# RX.net
KiCad netlist of a schematic drawn in Altium Designer
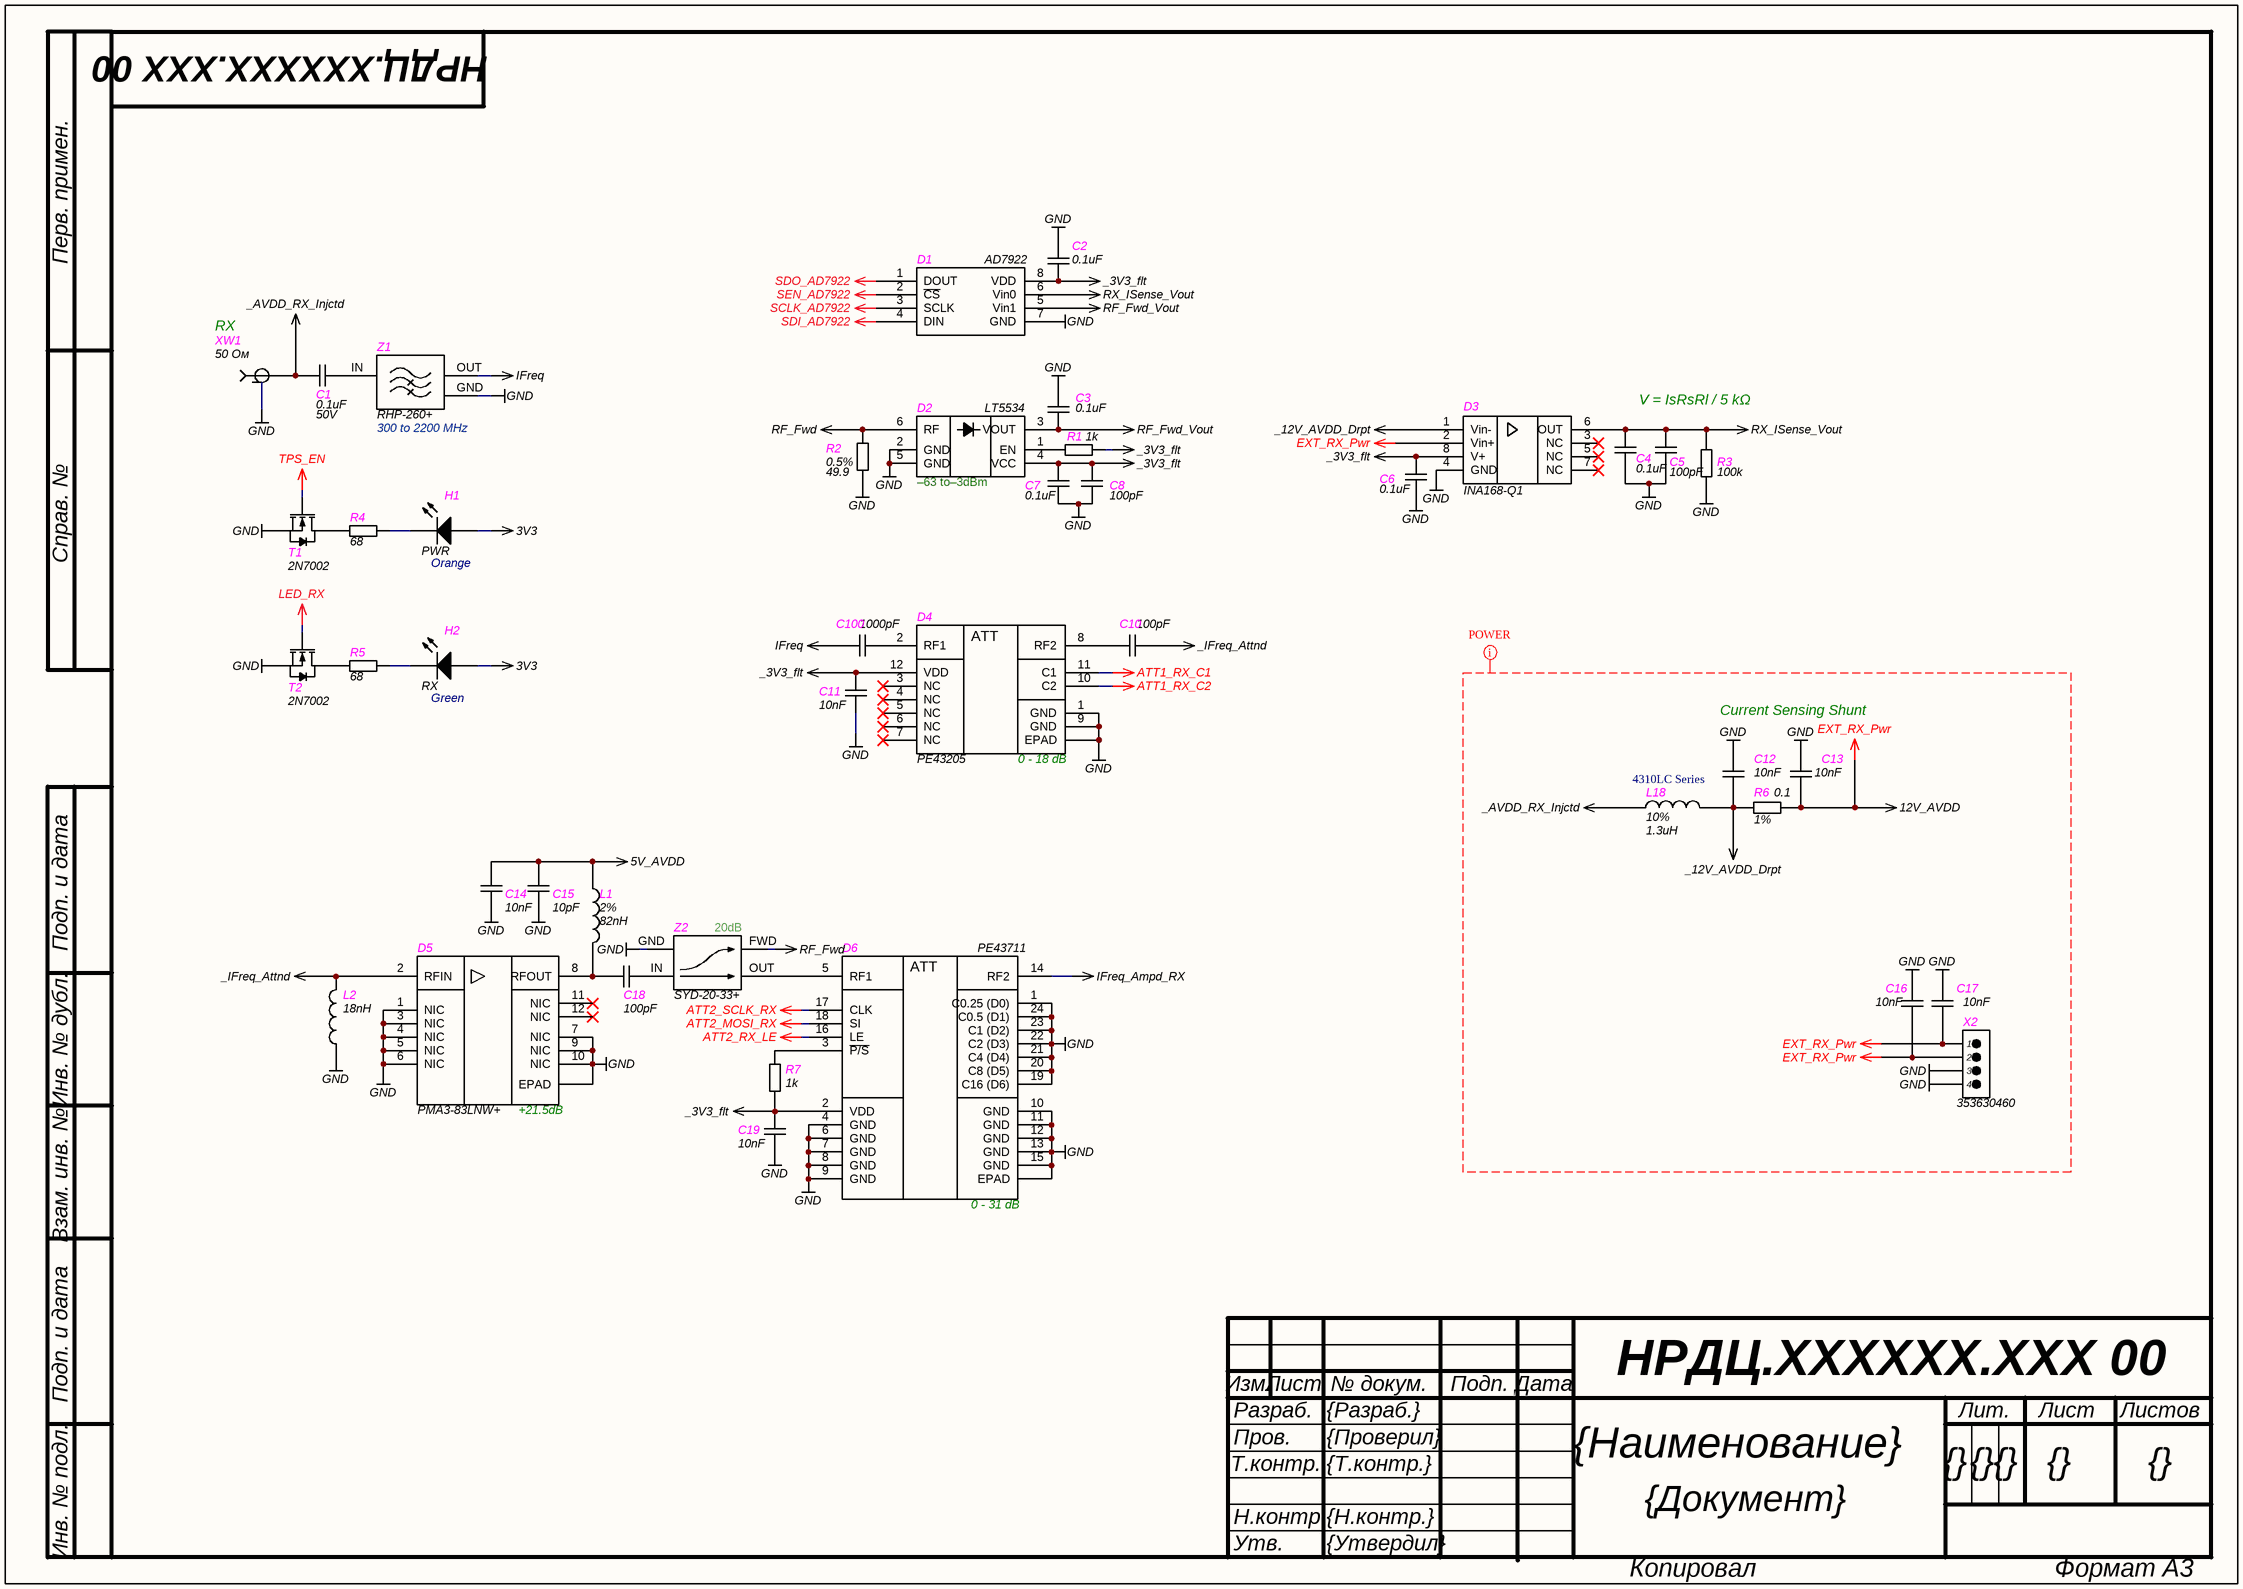
[diagram p0: RX.SchDoc]

(export (version "E")
  (design (tool "Eeschema 10.0.6"))
  (components
    (comp (ref "C1")
      (value "0.1uF")
      (footprint "C1206")
      (description "SMD Capacitor")
      (fields
        (field (name "MANUFACTURER") "Murata")
        (field (name "TOLERANCE") "5%")
        (field (name "VOLTAGE") "50V")
      )
      (libsource (lib "Kintex_SDR") (part "CAP"))
    )
    (comp (ref "C2")
      (value "0.1uF")
      (footprint "C0402")
      (description "SMD Capacitor")
      (fields (field (name "MANUFACTURER") "Murata") (field (name "TOLERANCE") "10%"))
      (libsource (lib "Kintex_SDR") (part "CAP"))
    )
    (comp (ref "C3")
      (value "0.1uF")
      (footprint "C0402")
      (description "SMD Capacitor")
      (fields (field (name "MANUFACTURER") "Murata") (field (name "TOLERANCE") "10%"))
      (libsource (lib "Kintex_SDR") (part "CAP"))
    )
    (comp (ref "C4")
      (value "0.1uF")
      (footprint "C0402")
      (description "SMD Capacitor")
      (fields (field (name "MANUFACTURER") "Murata") (field (name "TOLERANCE") "10%"))
      (libsource (lib "Kintex_SDR") (part "CAP"))
    )
    (comp (ref "C5")
      (value "100pF")
      (footprint "C0402")
      (description "SMD Capacitor")
      (fields (field (name "MANUFACTURER") "Murata") (field (name "TOLERANCE") "1%"))
      (libsource (lib "Kintex_SDR") (part "CAP"))
    )
    (comp (ref "C6")
      (value "0.1uF")
      (footprint "C0402")
      (description "SMD Capacitor")
      (fields (field (name "MANUFACTURER") "Murata") (field (name "TOLERANCE") "10%"))
      (libsource (lib "Kintex_SDR") (part "CAP"))
    )
    (comp (ref "C7")
      (value "0.1uF")
      (footprint "C0402")
      (description "SMD Capacitor")
      (fields (field (name "MANUFACTURER") "Murata") (field (name "TOLERANCE") "10%"))
      (libsource (lib "Kintex_SDR") (part "CAP"))
    )
    (comp (ref "C8")
      (value "100pF")
      (footprint "C0402")
      (description "SMD Capacitor")
      (fields (field (name "MANUFACTURER") "Murata") (field (name "TOLERANCE") "1%"))
      (libsource (lib "Kintex_SDR") (part "CAP"))
    )
    (comp (ref "C10")
      (value "100pF")
      (footprint "C0402")
      (description "SMD Capacitor")
      (fields (field (name "MANUFACTURER") "Murata") (field (name "TOLERANCE") "1%"))
      (libsource (lib "Kintex_SDR") (part "CAP"))
    )
    (comp (ref "C11")
      (value "10nF")
      (footprint "C0402")
      (description "SMD Capacitor")
      (fields (field (name "MANUFACTURER") "Murata") (field (name "TOLERANCE") "10%"))
      (libsource (lib "Kintex_SDR") (part "CAP"))
    )
    (comp (ref "C12")
      (value "10nF")
      (footprint "C0402")
      (description "SMD Capacitor")
      (fields (field (name "MANUFACTURER") "Murata") (field (name "TOLERANCE") "10%"))
      (libsource (lib "Kintex_SDR") (part "CAP"))
    )
    (comp (ref "C13")
      (value "10nF")
      (footprint "C0402")
      (description "SMD Capacitor")
      (fields (field (name "MANUFACTURER") "Murata") (field (name "TOLERANCE") "10%"))
      (libsource (lib "Kintex_SDR") (part "CAP"))
    )
    (comp (ref "C14")
      (value "10nF")
      (footprint "C0402")
      (description "SMD Capacitor")
      (fields (field (name "MANUFACTURER") "Murata") (field (name "TOLERANCE") "10%"))
      (libsource (lib "Kintex_SDR") (part "CAP"))
    )
    (comp (ref "C15")
      (value "10pF")
      (footprint "C0402")
      (description "SMD Capacitor")
      (fields (field (name "MANUFACTURER") "Murata") (field (name "TOLERANCE") "1%"))
      (libsource (lib "Kintex_SDR") (part "CAP"))
    )
    (comp (ref "C16")
      (value "10nF")
      (footprint "C0402")
      (description "SMD Capacitor")
      (fields (field (name "MANUFACTURER") "Murata") (field (name "TOLERANCE") "10%"))
      (libsource (lib "Kintex_SDR") (part "CAP"))
    )
    (comp (ref "C17")
      (value "10nF")
      (footprint "C0402")
      (description "SMD Capacitor")
      (fields (field (name "MANUFACTURER") "Murata") (field (name "TOLERANCE") "10%"))
      (libsource (lib "Kintex_SDR") (part "CAP"))
    )
    (comp (ref "C18")
      (value "100pF")
      (footprint "C0402")
      (description "SMD Capacitor")
      (fields (field (name "MANUFACTURER") "Murata") (field (name "TOLERANCE") "1%"))
      (libsource (lib "Kintex_SDR") (part "CAP"))
    )
    (comp (ref "C19")
      (value "10nF")
      (footprint "C0402")
      (description "SMD Capacitor")
      (fields (field (name "MANUFACTURER") "Murata") (field (name "TOLERANCE") "10%"))
      (libsource (lib "Kintex_SDR") (part "CAP"))
    )
    (comp (ref "C100")
      (value "1000pF")
      (footprint "C0402")
      (description "SMD Capacitor")
      (fields (field (name "MANUFACTURER") "Murata") (field (name "TOLERANCE") "5%"))
      (libsource (lib "Kintex_SDR") (part "CAP"))
    )
    (comp (ref "D1")
      (value "AD7922")
      (footprint "MSOP-8")
      (description "1 MSPS, 10-/12-Bit ADC")
      (fields (field (name "MANUFACTURER") "Analog Device") (field (name "VOLTAGE") "2.35 V to 5.25 V"))
      (libsource (lib "Kintex_SDR") (part "AD79x2"))
    )
    (comp (ref "D2")
      (value "LT5534")
      (footprint "DBLib:SC70")
      (description "50MHz to 3GHz monolithic RF power\r\ndetector")
      (fields
        (field (name "MANUFACTURER") "Linear Technology")
        (field (name "VOLTAGE") "Single 2.7V to 5.25V")
        (field (name "RF INPUT POWER RANGE") "–63 to–3dBm")
      )
      (libsource (lib "DBLib") (part "LT5534"))
    )
    (comp (ref "D3")
      (value "INA168-Q1")
      (footprint "DBLib:TSSOP (8)")
      (description "Automotive-Grade, High-Side, Current-Output, Current-Shunt Monitor")
      (fields (field (name "MANUFACTURER") "Texas Instruments") (field (name "VOLTAGE") "2.7 V to 60 V"))
      (libsource (lib "DBLib") (part "INA168-Q1"))
    )
    (comp (ref "D4")
      (value "PE43205")
      (footprint "DBLib:QFN-12")
      (description "50Ω, HaRP™ technology-enhanced\r\nfast switching 2-bit RF Digital Step Attenuator")
      (fields (field (name "MANUFACTURER") "Peregrine Technical Solutions"))
      (libsource (lib "DBLib") (part "PE43205"))
    )
    (comp (ref "D5")
      (value "PMA3-83LNW+")
      (footprint "DQ1225")
      (description "PHEMT based wideband, low noise MMIC amplifier")
      (fields (field (name "MANUFACTURER") "Mini-Circuits"))
      (libsource (lib "DBLib") (part "PMA3-83LNW+"))
    )
    (comp (ref "D6")
      (value "PE43711")
      (footprint "QFN-24")
      (description "The PE43711 is a 50Ω, HaRP™ technology-enhanced, 7-bit RF digital step attenuator")
      (fields (field (name "MANUFACTURER") "Peregrine Technical Solutions"))
      (libsource (lib "DBLib") (part "PE43711"))
    )
    (comp (ref "H1")
      (value "PWR")
      (footprint "LED_0805_Green")
      (description "CHIP LED LAMP")
      (fields (field (name "MANUFACTURER") "Kingbright") (field (name "COLOR") "Orange"))
      (libsource (lib "DBLib") (part "LED"))
    )
    (comp (ref "H2")
      (value "RX")
      (footprint "LED_0805_Green")
      (description "CHIP LED LAMP")
      (fields (field (name "MANUFACTURER") "Kingbright") (field (name "COLOR") "Green"))
      (libsource (lib "DBLib") (part "LED"))
    )
    (comp (ref "L1")
      (value "82nH")
      (footprint "DBLib:L0603_HP")
      (description "Chip SMD Inductor")
      (fields
        (field (name "MANUFACTURER") "Coilcraft")
        (field (name "TOLERANCE") "2%")
        (field (name "Comment") "Inductor RF")
      )
      (libsource (lib "DBLib") (part "Inductor RF"))
    )
    (comp (ref "L2")
      (value "18nH")
      (footprint "DBLib:L0603_HP")
      (description "Chip SMD Inductor")
      (fields (field (name "MANUFACTURER") "Coilcraft") (field (name "TOLERANCE") "2%"))
      (libsource (lib "") (part "Inductor RF_1"))
    )
    (comp (ref "L18")
      (value "1.3uH")
      (footprint "DBLib:4310LC")
      (description "Chip SMD Inductor")
      (fields
        (field (name "MANUFACTURER") "Coilcraft")
        (field (name "TOLERANCE") "10%")
        (field (name "Comment") "Inductor RF")
      )
      (libsource (lib "DBLib") (part "Inductor RF"))
    )
    (comp (ref "R1")
      (value "1k")
      (footprint "R0402")
      (description "SMD Resistor")
      (fields (field (name "POWER") "0.062 Wt") (field (name "TOLERANCE") "5%"))
      (libsource (lib "") (part "RES_1"))
    )
    (comp (ref "R2")
      (value "49.9")
      (footprint "R0402")
      (description "SMD Resistor")
      (fields
        (field (name "POWER") "0.063 Wt")
        (field (name "TOLERANCE") "0.5%")
        (field (name "MANUFACTURER") "Panasonic Electronic Components")
      )
      (libsource (lib "") (part "RES_3"))
    )
    (comp (ref "R3")
      (value "100k")
      (footprint "R0402")
      (description "SMD Resistor")
      (fields (field (name "POWER") "1/5 Wt") (field (name "TOLERANCE") "1%"))
      (libsource (lib "") (part "RES_2"))
    )
    (comp (ref "R4")
      (value "68")
      (footprint "R0402")
      (description "SMD Resistor")
      (fields (field (name "POWER") "0.062 Wt") (field (name "TOLERANCE") "5%"))
      (libsource (lib "Kintex_SDR") (part "RES"))
    )
    (comp (ref "R5")
      (value "68")
      (footprint "R0402")
      (description "SMD Resistor")
      (fields (field (name "POWER") "0.062 Wt") (field (name "TOLERANCE") "5%"))
      (libsource (lib "") (part "RES_1"))
    )
    (comp (ref "R6")
      (value "0.1")
      (footprint "R0805")
      (description "SMD Resistor")
      (fields
        (field (name "POWER") "1/2 Wt")
        (field (name "TOLERANCE") "1%")
        (field (name "MANUFACTURER") "Panasonic Electronic Components")
      )
      (libsource (lib "") (part "RES_1"))
    )
    (comp (ref "R7")
      (value "1k")
      (footprint "R0402")
      (description "SMD Resistor")
      (fields (field (name "POWER") "0.062 Wt") (field (name "TOLERANCE") "5%"))
      (libsource (lib "") (part "RES_2"))
    )
    (comp (ref "T1")
      (value "2N7002")
      (footprint "SOT-23")
      (description "N-Channel MOSFET 2N7002")
      (fields (field (name "VOLTAGE") "60V"))
      (libsource (lib "Kintex_SDR") (part "2N7002"))
    )
    (comp (ref "T2")
      (value "2N7002")
      (footprint "SOT-23")
      (description "N-Channel MOSFET 2N7002")
      (fields (field (name "VOLTAGE") "60V"))
      (libsource (lib "Kintex_SDR") (part "2N7002"))
    )
    (comp (ref "X2")
      (value "353630460")
      (footprint "DBLib:CON_353630460")
      (description "2.00mm Pitch Sherlock Wire-to-Board Header, Right-Angle, with Positive Lock, 4 Circuits")
      (fields (field (name "MANUFACTURER") "Molex"))
      (libsource (lib "DBLib") (part "353630460"))
    )
    (comp (ref "XW1")
      (value "50 Ом")
      (footprint "MOLEX SD-73251-135 (Gold)")
      (description "50 Ohms, SMA Jack, Vertica")
      (fields (field (name "MANUFACTURER") "Molex"))
      (libsource (lib "DBLib") (part "RF Connector"))
    )
    (comp (ref "Z1")
      (value "RHP-260+")
      (footprint "GP731")
      (description "High Pass Filter")
      (fields (field (name "MANUFACTURER") "Mini-Circuits") (field (name "FREQUENCY") "300 to 2200 MHz"))
      (libsource (lib "DBLib") (part "RHP-260+"))
    )
    (comp (ref "Z2")
      (value "SYD-20-33+")
      (footprint "DBLib:AH202")
      (description "Directional Coupler")
      (fields (field (name "MANUFACTURER") "Mini-Circuits") (field (name "COUPLING") "20dB"))
      (libsource (lib "DBLib") (part "SYD-20-33+"))
    )
  )
  (nets
    (net (code "1") (name "3V3") (class "Default")
      (node (ref "H1") (pin "2") (pinfunction "A_2") (pintype "passive"))
      (node (ref "H2") (pin "2") (pinfunction "A_2") (pintype "passive"))
    )
    (net (code "2") (name "5V_AVDD") (class "Default")
      (node (ref "C14") (pin "2") (pinfunction "2_2") (pintype "passive"))
      (node (ref "C15") (pin "2") (pinfunction "2_2") (pintype "passive"))
      (node (ref "L1") (pin "2") (pinfunction "2_2") (pintype "passive"))
    )
    (net (code "3") (name "12V_AVDD") (class "Default")
      (node (ref "C13") (pin "1") (pinfunction "1_1") (pintype "passive"))
      (node (ref "C16") (pin "2") (pinfunction "2_2") (pintype "passive"))
      (node (ref "C17") (pin "2") (pinfunction "2_2") (pintype "passive"))
      (node (ref "D3") (pin "2") (pinfunction "Vin+_2") (pintype "passive"))
      (node (ref "R6") (pin "1") (pinfunction "1_1") (pintype "passive"))
      (node (ref "X2") (pin "1") (pinfunction "1_1") (pintype "passive"))
      (node (ref "X2") (pin "2") (pinfunction "2_2") (pintype "passive"))
    )
    (net (code "4") (name "ATT1_RX_C1") (class "Default")
      (node (ref "D4") (pin "11") (pinfunction "C1_11") (pintype "passive"))
    )
    (net (code "5") (name "ATT1_RX_C2") (class "Default")
      (node (ref "D4") (pin "10") (pinfunction "C2_10") (pintype "passive"))
    )
    (net (code "6") (name "ATT2_MOSI_RX") (class "Default")
      (node (ref "D6") (pin "18") (pinfunction "SI_18") (pintype "passive"))
    )
    (net (code "7") (name "ATT2_RX_LE") (class "Default")
      (node (ref "D6") (pin "16") (pinfunction "LE_16") (pintype "passive"))
    )
    (net (code "8") (name "ATT2_SCLK_RX") (class "Default")
      (node (ref "D6") (pin "17") (pinfunction "CLK_17") (pintype "passive"))
    )
    (net (code "9") (name "GND") (class "Default")
      (node (ref "C11") (pin "1") (pinfunction "1_1") (pintype "passive"))
      (node (ref "C12") (pin "2") (pinfunction "2_2") (pintype "passive"))
      (node (ref "C13") (pin "2") (pinfunction "2_2") (pintype "passive"))
      (node (ref "C14") (pin "1") (pinfunction "1_1") (pintype "passive"))
      (node (ref "C15") (pin "1") (pinfunction "1_1") (pintype "passive"))
      (node (ref "C16") (pin "1") (pinfunction "1_1") (pintype "passive"))
      (node (ref "C17") (pin "1") (pinfunction "1_1") (pintype "passive"))
      (node (ref "C19") (pin "1") (pinfunction "1_1") (pintype "passive"))
      (node (ref "C2") (pin "2") (pinfunction "2_2") (pintype "passive"))
      (node (ref "C3") (pin "1") (pinfunction "1_1") (pintype "passive"))
      (node (ref "C4") (pin "1") (pinfunction "1_1") (pintype "passive"))
      (node (ref "C5") (pin "1") (pinfunction "1_1") (pintype "passive"))
      (node (ref "C6") (pin "1") (pinfunction "1_1") (pintype "passive"))
      (node (ref "C7") (pin "1") (pinfunction "1_1") (pintype "passive"))
      (node (ref "C8") (pin "1") (pinfunction "1_1") (pintype "passive"))
      (node (ref "D1") (pin "7") (pinfunction "GND_7") (pintype "passive"))
      (node (ref "D2") (pin "2") (pinfunction "GND_2") (pintype "passive"))
      (node (ref "D2") (pin "5") (pinfunction "GND_5") (pintype "passive"))
      (node (ref "D3") (pin "4") (pinfunction "GND_4") (pintype "passive"))
      (node (ref "D4") (pin "1") (pinfunction "GND_1") (pintype "passive"))
      (node (ref "D4") (pin "13") (pinfunction "EPAD_13") (pintype "passive"))
      (node (ref "D4") (pin "9") (pinfunction "GND_9") (pintype "passive"))
      (node (ref "D5") (pin "1") (pinfunction "NIC_1") (pintype "passive"))
      (node (ref "D5") (pin "10") (pinfunction "NIC_10") (pintype "passive"))
      (node (ref "D5") (pin "13") (pinfunction "EPAD_13") (pintype "passive"))
      (node (ref "D5") (pin "3") (pinfunction "NIC_3") (pintype "passive"))
      (node (ref "D5") (pin "4") (pinfunction "NIC_4") (pintype "passive"))
      (node (ref "D5") (pin "5") (pinfunction "NIC_5") (pintype "passive"))
      (node (ref "D5") (pin "6") (pinfunction "NIC_6") (pintype "passive"))
      (node (ref "D5") (pin "7") (pinfunction "NIC_7") (pintype "passive"))
      (node (ref "D5") (pin "9") (pinfunction "NIC_9") (pintype "passive"))
      (node (ref "D6") (pin "1") (pinfunction "C0.25_(D0)_1") (pintype "passive"))
      (node (ref "D6") (pin "10") (pinfunction "GND_10") (pintype "passive"))
      (node (ref "D6") (pin "11") (pinfunction "GND_11") (pintype "passive"))
      (node (ref "D6") (pin "12") (pinfunction "GND_12") (pintype "passive"))
      (node (ref "D6") (pin "13") (pinfunction "GND_13") (pintype "passive"))
      (node (ref "D6") (pin "15") (pinfunction "GND_15") (pintype "passive"))
      (node (ref "D6") (pin "19") (pinfunction "C16_(D6)_19") (pintype "passive"))
      (node (ref "D6") (pin "20") (pinfunction "C8_(D5)_20") (pintype "passive"))
      (node (ref "D6") (pin "21") (pinfunction "C4_(D4)_21") (pintype "passive"))
      (node (ref "D6") (pin "22") (pinfunction "C2_(D3)_22") (pintype "passive"))
      (node (ref "D6") (pin "23") (pinfunction "C1_(D2)_23") (pintype "passive"))
      (node (ref "D6") (pin "24") (pinfunction "C0.5_(D1)_24") (pintype "passive"))
      (node (ref "D6") (pin "25") (pinfunction "EPAD_25") (pintype "passive"))
      (node (ref "D6") (pin "4") (pinfunction "GND_4") (pintype "passive"))
      (node (ref "D6") (pin "6") (pinfunction "GND_6") (pintype "passive"))
      (node (ref "D6") (pin "7") (pinfunction "GND_7") (pintype "passive"))
      (node (ref "D6") (pin "8") (pinfunction "GND_8") (pintype "passive"))
      (node (ref "D6") (pin "9") (pinfunction "GND_9") (pintype "passive"))
      (node (ref "L2") (pin "1") (pinfunction "1_1") (pintype "passive"))
      (node (ref "R2") (pin "2") (pinfunction "2_2") (pintype "passive"))
      (node (ref "R3") (pin "1") (pinfunction "1_1") (pintype "passive"))
      (node (ref "T1") (pin "2") (pinfunction "S_2") (pintype "passive"))
      (node (ref "T2") (pin "2") (pinfunction "S_2") (pintype "passive"))
      (node (ref "X2") (pin "3") (pinfunction "3_3") (pintype "passive"))
      (node (ref "X2") (pin "4") (pinfunction "4_4") (pintype "passive"))
      (node (ref "XW1") (pin "G") (pinfunction "GND_G") (pintype "passive"))
      (node (ref "Z1") (pin "GND") (pinfunction "GND_GND") (pintype "passive"))
      (node (ref "Z2") (pin "GND") (pinfunction "GND_GND") (pintype "passive"))
    )
    (net (code "10") (name "IFreq") (class "Default")
      (node (ref "C100") (pin "1") (pinfunction "1_1") (pintype "passive"))
      (node (ref "Z1") (pin "OUT") (pinfunction "OUT_OUT") (pintype "passive"))
    )
    (net (code "11") (name "IFreq_Ampd_RX") (class "Default")
      (node (ref "D6") (pin "14") (pinfunction "RF2_14") (pintype "passive"))
    )
    (net (code "12") (name "LED_RX") (class "Default")
      (node (ref "T2") (pin "1") (pinfunction "G_1") (pintype "passive"))
    )
    (net (code "13") (name "Net-(C1-Pad2)") (class "Default")
      (node (ref "C1") (pin "2") (pinfunction "2_2") (pintype "passive"))
      (node (ref "Z1") (pin "IN") (pinfunction "IN_IN") (pintype "passive"))
    )
    (net (code "14") (name "Net-(C18-Pad2)") (class "Default")
      (node (ref "C18") (pin "2") (pinfunction "2_2") (pintype "passive"))
      (node (ref "Z2") (pin "IN") (pinfunction "IN_IN") (pintype "passive"))
    )
    (net (code "15") (name "Net-(D2-EN)") (class "Default")
      (node (ref "D2") (pin "1") (pinfunction "EN_1") (pintype "passive"))
      (node (ref "R1") (pin "2") (pinfunction "2_2") (pintype "passive"))
    )
    (net (code "16") (name "Net-(D4-RF1)") (class "Default")
      (node (ref "C100") (pin "2") (pinfunction "2_2") (pintype "passive"))
      (node (ref "D4") (pin "2") (pinfunction "RF1_2") (pintype "passive"))
    )
    (net (code "17") (name "Net-(D4-RF2)") (class "Default")
      (node (ref "C10") (pin "1") (pinfunction "1_1") (pintype "passive"))
      (node (ref "D4") (pin "8") (pinfunction "RF2_8") (pintype "passive"))
    )
    (net (code "18") (name "Net-(D5-RFOUT)") (class "Default")
      (node (ref "C18") (pin "1") (pinfunction "1_1") (pintype "passive"))
      (node (ref "D5") (pin "8") (pinfunction "RFOUT_8") (pintype "passive"))
      (node (ref "L1") (pin "1") (pinfunction "1_1") (pintype "passive"))
    )
    (net (code "19") (name "Net-(D6-RF1)") (class "Default")
      (node (ref "D6") (pin "5") (pinfunction "RF1_5") (pintype "passive"))
      (node (ref "Z2") (pin "OUT") (pinfunction "OUT_OUT") (pintype "passive"))
    )
    (net (code "20") (name "Net-(D6-~{P{slash}S})") (class "Default")
      (node (ref "D6") (pin "3") (pinfunction "~{P/S}_3") (pintype "passive"))
      (node (ref "R7") (pin "2") (pinfunction "2_2") (pintype "passive"))
    )
    (net (code "21") (name "Net-(H1-K)") (class "Default")
      (node (ref "H1") (pin "1") (pinfunction "K_1") (pintype "passive"))
      (node (ref "R4") (pin "2") (pinfunction "2_2") (pintype "passive"))
    )
    (net (code "22") (name "Net-(H2-K)") (class "Default")
      (node (ref "H2") (pin "1") (pinfunction "K_1") (pintype "passive"))
      (node (ref "R5") (pin "1") (pinfunction "1_1") (pintype "passive"))
    )
    (net (code "23") (name "Net-(T1-D)") (class "Default")
      (node (ref "R4") (pin "1") (pinfunction "1_1") (pintype "passive"))
      (node (ref "T1") (pin "3") (pinfunction "D_3") (pintype "passive"))
    )
    (net (code "24") (name "Net-(T2-D)") (class "Default")
      (node (ref "R5") (pin "2") (pinfunction "2_2") (pintype "passive"))
      (node (ref "T2") (pin "3") (pinfunction "D_3") (pintype "passive"))
    )
    (net (code "25") (name "RF_Fwd") (class "Default")
      (node (ref "D2") (pin "6") (pinfunction "RF_6") (pintype "passive"))
      (node (ref "R2") (pin "1") (pinfunction "1_1") (pintype "passive"))
      (node (ref "Z2") (pin "FWD") (pinfunction "FWD_FWD") (pintype "passive"))
    )
    (net (code "26") (name "RF_Fwd_Vout") (class "Default")
      (node (ref "C3") (pin "2") (pinfunction "2_2") (pintype "passive"))
      (node (ref "D1") (pin "5") (pinfunction "Vin1_5") (pintype "passive"))
      (node (ref "D2") (pin "3") (pinfunction "VOUT_3") (pintype "passive"))
    )
    (net (code "27") (name "RX_ISense_Vout") (class "Default")
      (node (ref "C4") (pin "2") (pinfunction "2_2") (pintype "passive"))
      (node (ref "C5") (pin "2") (pinfunction "2_2") (pintype "passive"))
      (node (ref "D1") (pin "6") (pinfunction "Vin0_6") (pintype "passive"))
      (node (ref "D3") (pin "6") (pinfunction "OUT_6") (pintype "passive"))
      (node (ref "R3") (pin "2") (pinfunction "2_2") (pintype "passive"))
    )
    (net (code "28") (name "SCLK_AD7922") (class "Default")
      (node (ref "D1") (pin "3") (pinfunction "SCLK_3") (pintype "passive"))
    )
    (net (code "29") (name "SDI_AD7922") (class "Default")
      (node (ref "D1") (pin "4") (pinfunction "DIN_4") (pintype "passive"))
    )
    (net (code "30") (name "SDO_AD7922") (class "Default")
      (node (ref "D1") (pin "1") (pinfunction "DOUT_1") (pintype "passive"))
    )
    (net (code "31") (name "SEN_AD7922") (class "Default")
      (node (ref "D1") (pin "2") (pinfunction "~{CS}_2") (pintype "passive"))
    )
    (net (code "32") (name "TPS_EN") (class "Default")
      (node (ref "T1") (pin "1") (pinfunction "G_1") (pintype "passive"))
    )
    (net (code "33") (name "_3V3_flt") (class "Default")
      (node (ref "C11") (pin "2") (pinfunction "2_2") (pintype "passive"))
      (node (ref "C19") (pin "2") (pinfunction "2_2") (pintype "passive"))
      (node (ref "C2") (pin "1") (pinfunction "1_1") (pintype "passive"))
      (node (ref "C6") (pin "2") (pinfunction "2_2") (pintype "passive"))
      (node (ref "C7") (pin "2") (pinfunction "2_2") (pintype "passive"))
      (node (ref "C8") (pin "2") (pinfunction "2_2") (pintype "passive"))
      (node (ref "D1") (pin "8") (pinfunction "VDD_8") (pintype "passive"))
      (node (ref "D2") (pin "4") (pinfunction "VCC_4") (pintype "passive"))
      (node (ref "D3") (pin "8") (pinfunction "V+_8") (pintype "passive"))
      (node (ref "D4") (pin "12") (pinfunction "VDD_12") (pintype "passive"))
      (node (ref "D6") (pin "2") (pinfunction "VDD_2") (pintype "passive"))
      (node (ref "R1") (pin "1") (pinfunction "1_1") (pintype "passive"))
      (node (ref "R7") (pin "1") (pinfunction "1_1") (pintype "passive"))
    )
    (net (code "34") (name "_12V_AVDD_Drpt") (class "Default")
      (node (ref "C12") (pin "1") (pinfunction "1_1") (pintype "passive"))
      (node (ref "D3") (pin "1") (pinfunction "Vin-_1") (pintype "passive"))
      (node (ref "L18") (pin "1") (pinfunction "1_1") (pintype "passive"))
      (node (ref "R6") (pin "2") (pinfunction "2_2") (pintype "passive"))
    )
    (net (code "35") (name "_AVDD_RX_Injctd") (class "Default")
      (node (ref "C1") (pin "1") (pinfunction "1_1") (pintype "passive"))
      (node (ref "L18") (pin "2") (pinfunction "2_2") (pintype "passive"))
      (node (ref "XW1") (pin "S") (pinfunction "RF_S") (pintype "passive"))
    )
    (net (code "36") (name "_IFreq_Attnd") (class "Default")
      (node (ref "C10") (pin "2") (pinfunction "2_2") (pintype "passive"))
      (node (ref "D5") (pin "2") (pinfunction "RFIN_2") (pintype "passive"))
      (node (ref "L2") (pin "2") (pinfunction "2_2") (pintype "passive"))
    )
    (net (code "37") (name "unconnected-(D3-NC-Pad3)") (class "Default")
      (node (ref "D3") (pin "3") (pinfunction "NC_3") (pintype "passive+no_connect"))
    )
    (net (code "38") (name "unconnected-(D3-NC-Pad5)") (class "Default")
      (node (ref "D3") (pin "5") (pinfunction "NC_5") (pintype "passive+no_connect"))
    )
    (net (code "39") (name "unconnected-(D3-NC-Pad7)") (class "Default")
      (node (ref "D3") (pin "7") (pinfunction "NC_7") (pintype "passive+no_connect"))
    )
    (net (code "40") (name "unconnected-(D4-NC-Pad3)") (class "Default")
      (node (ref "D4") (pin "3") (pinfunction "NC_3") (pintype "passive+no_connect"))
    )
    (net (code "41") (name "unconnected-(D4-NC-Pad4)") (class "Default")
      (node (ref "D4") (pin "4") (pinfunction "NC_4") (pintype "passive+no_connect"))
    )
    (net (code "42") (name "unconnected-(D4-NC-Pad5)") (class "Default")
      (node (ref "D4") (pin "5") (pinfunction "NC_5") (pintype "passive+no_connect"))
    )
    (net (code "43") (name "unconnected-(D4-NC-Pad6)") (class "Default")
      (node (ref "D4") (pin "6") (pinfunction "NC_6") (pintype "passive+no_connect"))
    )
    (net (code "44") (name "unconnected-(D4-NC-Pad7)") (class "Default")
      (node (ref "D4") (pin "7") (pinfunction "NC_7") (pintype "passive+no_connect"))
    )
    (net (code "45") (name "unconnected-(D5-NIC-Pad11)") (class "Default")
      (node (ref "D5") (pin "11") (pinfunction "NIC_11") (pintype "passive+no_connect"))
    )
    (net (code "46") (name "unconnected-(D5-NIC-Pad12)") (class "Default")
      (node (ref "D5") (pin "12") (pinfunction "NIC_12") (pintype "passive+no_connect"))
    )
  )
)
